# O2.net
KiCad netlist of a schematic drawn in EAGLE
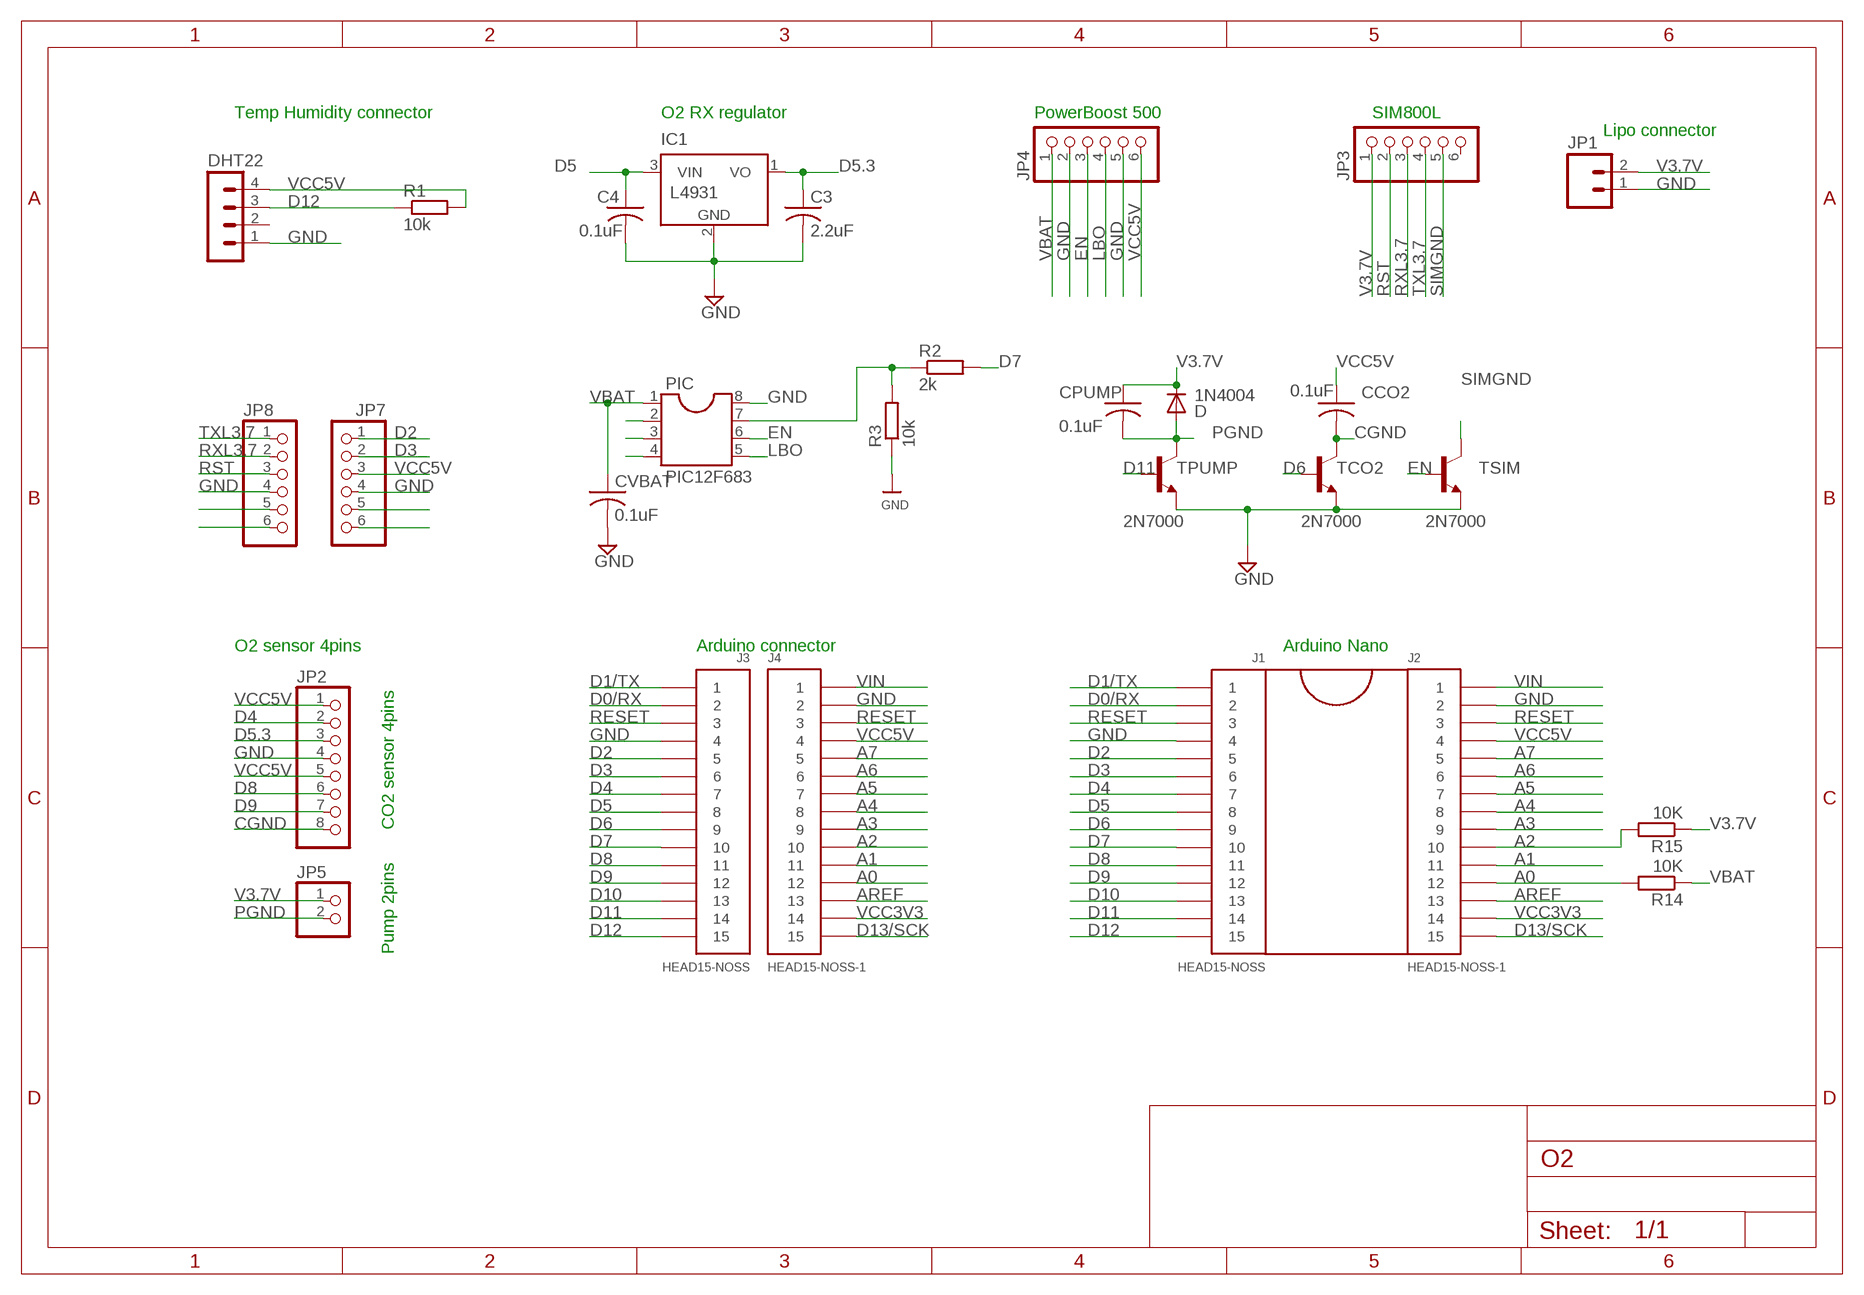
[diagram p0: schematic, sheet 1]

(export (version "E")
  (design (tool "Eeschema 10.0.6"))
  (components
    (comp (ref "C3")
      (value "2.2uF")
      (footprint "eagle-import:C025-030X050")
      (libsource (lib "eagle-import") (part "C-US025-030X050"))
    )
    (comp (ref "C4")
      (value "0.1uF")
      (footprint "eagle-import:C025-030X050")
      (libsource (lib "eagle-import") (part "C-US025-030X050"))
    )
    (comp (ref "CCO2")
      (value "0.1uF")
      (footprint "eagle-import:C025-030X050")
      (libsource (lib "eagle-import") (part "C-US025-030X050"))
    )
    (comp (ref "CPUMP")
      (value "0.1uF")
      (footprint "eagle-import:C025-030X050")
      (libsource (lib "eagle-import") (part "C-US025-030X050"))
    )
    (comp (ref "CVBAT")
      (value "0.1uF")
      (footprint "eagle-import:C025-030X050")
      (libsource (lib "eagle-import") (part "C-US025-030X050"))
    )
    (comp (ref "D")
      (value "1N4004")
      (footprint "eagle-import:DO41-10")
      (libsource (lib "eagle-import") (part "1N4004"))
    )
    (comp (ref "DHT22")
      (value "MA04-1")
      (footprint "eagle-import:MA04-1")
      (libsource (lib "eagle-import") (part "MA04-1"))
    )
    (comp (ref "IC1")
      (value "L4931")
      (footprint "eagle-import:TO92")
      (fields (field (name "MF") "NATIONAL SEMICONDUCTOR") (field (name "MPN") "LM2936Z-3.3/NOPB"))
      (libsource (lib "eagle-import") (part "LM2936?Z-3.3"))
    )
    (comp (ref "J1")
      (value "HEAD15-NOSS")
      (footprint "eagle-import:HEAD15-NOSS")
      (libsource (lib "eagle-import") (part "HEAD15-NOSS"))
    )
    (comp (ref "J2")
      (value "HEAD15-NOSS-1")
      (footprint "eagle-import:HEAD15-NOSS-1")
      (libsource (lib "eagle-import") (part "HEAD15-NOSS-1"))
    )
    (comp (ref "J3")
      (value "HEAD15-NOSS")
      (footprint "eagle-import:HEAD15-NOSS")
      (libsource (lib "eagle-import") (part "HEAD15-NOSS"))
    )
    (comp (ref "J4")
      (value "HEAD15-NOSS-1")
      (footprint "eagle-import:HEAD15-NOSS-1")
      (libsource (lib "eagle-import") (part "HEAD15-NOSS-1"))
    )
    (comp (ref "JP1")
      (value "M023.5MM")
      (footprint "eagle-import:SCREWTERMINAL-3.5MM-2")
      (libsource (lib "eagle-import") (part "M023.5MM"))
    )
    (comp (ref "JP2")
      (value "PINHD-1X8BIG")
      (footprint "eagle-import:1X08-BIG")
      (libsource (lib "eagle-import") (part "PINHD-1X8BIG"))
    )
    (comp (ref "JP3")
      (value "PINHD-1X6CB")
      (footprint "eagle-import:1X06-CLEANBIG")
      (libsource (lib "eagle-import") (part "PINHD-1X6CB"))
    )
    (comp (ref "JP4")
      (value "PINHD-1X6CB")
      (footprint "eagle-import:1X06-CLEANBIG")
      (libsource (lib "eagle-import") (part "PINHD-1X6CB"))
    )
    (comp (ref "JP5")
      (value "PINHD-1X2")
      (footprint "eagle-import:1X02")
      (libsource (lib "eagle-import") (part "PINHD-1X2"))
    )
    (comp (ref "JP7")
      (value "PINHD-1X6CB")
      (footprint "eagle-import:1X06-CLEANBIG")
      (libsource (lib "eagle-import") (part "PINHD-1X6CB"))
    )
    (comp (ref "JP8")
      (value "PINHD-1X6CB")
      (footprint "eagle-import:1X06-CLEANBIG")
      (libsource (lib "eagle-import") (part "PINHD-1X6CB"))
    )
    (comp (ref "PIC")
      (value "PIC12F683")
      (footprint "eagle-import:SOCKET-08")
      (libsource (lib "eagle-import") (part "DIL8S"))
    )
    (comp (ref "R1")
      (value "10k")
      (footprint "eagle-import:0204_5")
      (libsource (lib "eagle-import") (part "R-EU_0204/5"))
    )
    (comp (ref "R2")
      (value "2k")
      (footprint "eagle-import:0204_5")
      (libsource (lib "eagle-import") (part "R-EU_0204/5"))
    )
    (comp (ref "R3")
      (value "10k")
      (footprint "eagle-import:0204_5")
      (libsource (lib "eagle-import") (part "R-EU_0204/5"))
    )
    (comp (ref "R14")
      (value "10K")
      (footprint "eagle-import:0204_5")
      (libsource (lib "eagle-import") (part "R-EU_0204/5"))
    )
    (comp (ref "R15")
      (value "10K")
      (footprint "eagle-import:0204_5")
      (libsource (lib "eagle-import") (part "R-EU_0204/5"))
    )
    (comp (ref "TCO2")
      (value "2N7000")
      (footprint "eagle-import:TO92-EBC-OVAL")
      (libsource (lib "eagle-import") (part "2N2222"))
    )
    (comp (ref "TPUMP")
      (value "2N7000")
      (footprint "eagle-import:TO92-EBC-OVAL")
      (libsource (lib "eagle-import") (part "2N2222"))
    )
    (comp (ref "TSIM")
      (value "2N7000")
      (footprint "eagle-import:TO92-EBC-OVAL")
      (libsource (lib "eagle-import") (part "2N2222"))
    )
  )
  (nets
    (net (code "1") (name "/A0") (class "Default")
      (node (ref "J2") (pin "12") (pinfunction "12_12") (pintype "passive"))
      (node (ref "J4") (pin "12") (pinfunction "12_12") (pintype "passive"))
      (node (ref "R14") (pin "2") (pinfunction "2_2") (pintype "passive"))
    )
    (net (code "2") (name "/A1") (class "Default")
      (node (ref "J2") (pin "11") (pinfunction "11_11") (pintype "passive"))
      (node (ref "J4") (pin "11") (pinfunction "11_11") (pintype "passive"))
    )
    (net (code "3") (name "/A2") (class "Default")
      (node (ref "J2") (pin "10") (pinfunction "10_10") (pintype "passive"))
      (node (ref "J4") (pin "10") (pinfunction "10_10") (pintype "passive"))
      (node (ref "R15") (pin "2") (pinfunction "2_2") (pintype "passive"))
    )
    (net (code "4") (name "/A3") (class "Default")
      (node (ref "J2") (pin "9") (pinfunction "9_9") (pintype "passive"))
      (node (ref "J4") (pin "9") (pinfunction "9_9") (pintype "passive"))
    )
    (net (code "5") (name "/A4") (class "Default")
      (node (ref "J2") (pin "8") (pinfunction "8_8") (pintype "passive"))
      (node (ref "J4") (pin "8") (pinfunction "8_8") (pintype "passive"))
    )
    (net (code "6") (name "/A5") (class "Default")
      (node (ref "J2") (pin "7") (pinfunction "7_7") (pintype "passive"))
      (node (ref "J4") (pin "7") (pinfunction "7_7") (pintype "passive"))
    )
    (net (code "7") (name "/A6") (class "Default")
      (node (ref "J2") (pin "6") (pinfunction "6_6") (pintype "passive"))
      (node (ref "J4") (pin "6") (pinfunction "6_6") (pintype "passive"))
    )
    (net (code "8") (name "/A7") (class "Default")
      (node (ref "J2") (pin "5") (pinfunction "5_5") (pintype "passive"))
      (node (ref "J4") (pin "5") (pinfunction "5_5") (pintype "passive"))
    )
    (net (code "9") (name "/AREF") (class "Default")
      (node (ref "J2") (pin "13") (pinfunction "13_13") (pintype "passive"))
      (node (ref "J4") (pin "13") (pinfunction "13_13") (pintype "passive"))
    )
    (net (code "10") (name "/CGND") (class "Default")
      (node (ref "CCO2") (pin "2") (pinfunction "2_2") (pintype "passive"))
      (node (ref "JP2") (pin "8") (pinfunction "8_8") (pintype "passive"))
      (node (ref "TCO2") (pin "C") (pinfunction "C_C") (pintype "passive"))
    )
    (net (code "11") (name "/D0{slash}RX") (class "Default")
      (node (ref "J1") (pin "2") (pinfunction "2_2") (pintype "passive"))
      (node (ref "J3") (pin "2") (pinfunction "2_2") (pintype "passive"))
    )
    (net (code "12") (name "/D1{slash}TX") (class "Default")
      (node (ref "J1") (pin "1") (pinfunction "1_1") (pintype "passive"))
      (node (ref "J3") (pin "1") (pinfunction "1_1") (pintype "passive"))
    )
    (net (code "13") (name "/D2") (class "Default")
      (node (ref "J1") (pin "5") (pinfunction "5_5") (pintype "passive"))
      (node (ref "J3") (pin "5") (pinfunction "5_5") (pintype "passive"))
      (node (ref "JP7") (pin "1") (pinfunction "1_1") (pintype "passive"))
    )
    (net (code "14") (name "/D3") (class "Default")
      (node (ref "J1") (pin "6") (pinfunction "6_6") (pintype "passive"))
      (node (ref "J3") (pin "6") (pinfunction "6_6") (pintype "passive"))
      (node (ref "JP7") (pin "2") (pinfunction "2_2") (pintype "passive"))
    )
    (net (code "15") (name "/D4") (class "Default")
      (node (ref "J1") (pin "7") (pinfunction "7_7") (pintype "passive"))
      (node (ref "J3") (pin "7") (pinfunction "7_7") (pintype "passive"))
      (node (ref "JP2") (pin "2") (pinfunction "2_2") (pintype "passive"))
    )
    (net (code "16") (name "/D5") (class "Default")
      (node (ref "C4") (pin "1") (pinfunction "1_1") (pintype "passive"))
      (node (ref "IC1") (pin "3") (pinfunction "VIN_3") (pintype "input"))
      (node (ref "J1") (pin "8") (pinfunction "8_8") (pintype "passive"))
      (node (ref "J3") (pin "8") (pinfunction "8_8") (pintype "passive"))
    )
    (net (code "17") (name "/D5.3") (class "Default")
      (node (ref "C3") (pin "1") (pinfunction "1_1") (pintype "passive"))
      (node (ref "IC1") (pin "1") (pinfunction "VO_1") (pintype "passive"))
      (node (ref "JP2") (pin "3") (pinfunction "3_3") (pintype "passive"))
    )
    (net (code "18") (name "/D6") (class "Default")
      (node (ref "J1") (pin "9") (pinfunction "9_9") (pintype "passive"))
      (node (ref "J3") (pin "9") (pinfunction "9_9") (pintype "passive"))
      (node (ref "TCO2") (pin "B") (pinfunction "B_B") (pintype "passive"))
    )
    (net (code "19") (name "/D7") (class "Default")
      (node (ref "J1") (pin "10") (pinfunction "10_10") (pintype "passive"))
      (node (ref "J3") (pin "10") (pinfunction "10_10") (pintype "passive"))
      (node (ref "R2") (pin "2") (pinfunction "2_2") (pintype "passive"))
    )
    (net (code "20") (name "/D8") (class "Default")
      (node (ref "J1") (pin "11") (pinfunction "11_11") (pintype "passive"))
      (node (ref "J3") (pin "11") (pinfunction "11_11") (pintype "passive"))
      (node (ref "JP2") (pin "6") (pinfunction "6_6") (pintype "passive"))
    )
    (net (code "21") (name "/D9") (class "Default")
      (node (ref "J1") (pin "12") (pinfunction "12_12") (pintype "passive"))
      (node (ref "J3") (pin "12") (pinfunction "12_12") (pintype "passive"))
      (node (ref "JP2") (pin "7") (pinfunction "7_7") (pintype "passive"))
    )
    (net (code "22") (name "/D10") (class "Default")
      (node (ref "J1") (pin "13") (pinfunction "13_13") (pintype "passive"))
      (node (ref "J3") (pin "13") (pinfunction "13_13") (pintype "passive"))
    )
    (net (code "23") (name "/D11") (class "Default")
      (node (ref "J1") (pin "14") (pinfunction "14_14") (pintype "passive"))
      (node (ref "J3") (pin "14") (pinfunction "14_14") (pintype "passive"))
      (node (ref "TPUMP") (pin "B") (pinfunction "B_B") (pintype "passive"))
    )
    (net (code "24") (name "/D12") (class "Default")
      (node (ref "DHT22") (pin "3") (pinfunction "3_3") (pintype "passive"))
      (node (ref "J1") (pin "15") (pinfunction "15_15") (pintype "passive"))
      (node (ref "J3") (pin "15") (pinfunction "15_15") (pintype "passive"))
      (node (ref "R1") (pin "1") (pinfunction "1_1") (pintype "passive"))
    )
    (net (code "25") (name "/D13{slash}SCK") (class "Default")
      (node (ref "J2") (pin "15") (pinfunction "15_15") (pintype "passive"))
      (node (ref "J4") (pin "15") (pinfunction "15_15") (pintype "passive"))
    )
    (net (code "26") (name "/EN") (class "Default")
      (node (ref "JP4") (pin "3") (pinfunction "3_3") (pintype "passive"))
      (node (ref "PIC") (pin "6") (pinfunction "6_6") (pintype "passive"))
      (node (ref "TSIM") (pin "B") (pinfunction "B_B") (pintype "passive"))
    )
    (net (code "27") (name "/LBO") (class "Default")
      (node (ref "JP4") (pin "4") (pinfunction "4_4") (pintype "passive"))
      (node (ref "PIC") (pin "5") (pinfunction "5_5") (pintype "passive"))
    )
    (net (code "28") (name "/PGND") (class "Default")
      (node (ref "CPUMP") (pin "2") (pinfunction "2_2") (pintype "passive"))
      (node (ref "D") (pin "A") (pinfunction "A_A") (pintype "passive"))
      (node (ref "JP5") (pin "2") (pinfunction "2_2") (pintype "passive"))
      (node (ref "TPUMP") (pin "C") (pinfunction "C_C") (pintype "passive"))
    )
    (net (code "29") (name "/RESET") (class "Default")
      (node (ref "J1") (pin "3") (pinfunction "3_3") (pintype "passive"))
      (node (ref "J2") (pin "3") (pinfunction "3_3") (pintype "passive"))
      (node (ref "J3") (pin "3") (pinfunction "3_3") (pintype "passive"))
      (node (ref "J4") (pin "3") (pinfunction "3_3") (pintype "passive"))
    )
    (net (code "30") (name "/RST") (class "Default")
      (node (ref "JP3") (pin "2") (pinfunction "2_2") (pintype "passive"))
      (node (ref "JP8") (pin "3") (pinfunction "3_3") (pintype "passive"))
    )
    (net (code "31") (name "/RXL3.7") (class "Default")
      (node (ref "JP3") (pin "3") (pinfunction "3_3") (pintype "passive"))
      (node (ref "JP8") (pin "2") (pinfunction "2_2") (pintype "passive"))
    )
    (net (code "32") (name "/SIMGND") (class "Default")
      (node (ref "JP3") (pin "5") (pinfunction "5_5") (pintype "passive"))
      (node (ref "TSIM") (pin "C") (pinfunction "C_C") (pintype "passive"))
    )
    (net (code "33") (name "/TXL3.7") (class "Default")
      (node (ref "JP3") (pin "4") (pinfunction "4_4") (pintype "passive"))
      (node (ref "JP8") (pin "1") (pinfunction "1_1") (pintype "passive"))
    )
    (net (code "34") (name "/V3.7V") (class "Default")
      (node (ref "CPUMP") (pin "1") (pinfunction "1_1") (pintype "passive"))
      (node (ref "D") (pin "C") (pinfunction "C_C") (pintype "passive"))
      (node (ref "JP1") (pin "2") (pinfunction "2_2") (pintype "passive"))
      (node (ref "JP3") (pin "1") (pinfunction "1_1") (pintype "passive"))
      (node (ref "JP5") (pin "1") (pinfunction "1_1") (pintype "passive"))
      (node (ref "R15") (pin "1") (pinfunction "1_1") (pintype "passive"))
    )
    (net (code "35") (name "/VBAT") (class "Default")
      (node (ref "CVBAT") (pin "1") (pinfunction "1_1") (pintype "passive"))
      (node (ref "JP4") (pin "1") (pinfunction "1_1") (pintype "passive"))
      (node (ref "PIC") (pin "1") (pinfunction "1_1") (pintype "passive"))
      (node (ref "R14") (pin "1") (pinfunction "1_1") (pintype "passive"))
    )
    (net (code "36") (name "/VCC3V3") (class "Default")
      (node (ref "J2") (pin "14") (pinfunction "14_14") (pintype "passive"))
      (node (ref "J4") (pin "14") (pinfunction "14_14") (pintype "passive"))
    )
    (net (code "37") (name "/VCC5V") (class "Default")
      (node (ref "CCO2") (pin "1") (pinfunction "1_1") (pintype "passive"))
      (node (ref "DHT22") (pin "4") (pinfunction "4_4") (pintype "passive"))
      (node (ref "J2") (pin "4") (pinfunction "4_4") (pintype "passive"))
      (node (ref "J4") (pin "4") (pinfunction "4_4") (pintype "passive"))
      (node (ref "JP2") (pin "1") (pinfunction "1_1") (pintype "passive"))
      (node (ref "JP2") (pin "5") (pinfunction "5_5") (pintype "passive"))
      (node (ref "JP4") (pin "6") (pinfunction "6_6") (pintype "passive"))
      (node (ref "JP7") (pin "3") (pinfunction "3_3") (pintype "passive"))
      (node (ref "R1") (pin "2") (pinfunction "2_2") (pintype "passive"))
    )
    (net (code "38") (name "/VIN") (class "Default")
      (node (ref "J2") (pin "1") (pinfunction "1_1") (pintype "passive"))
      (node (ref "J4") (pin "1") (pinfunction "1_1") (pintype "passive"))
    )
    (net (code "39") (name "GND") (class "Default")
      (node (ref "C3") (pin "2") (pinfunction "2_2") (pintype "passive"))
      (node (ref "C4") (pin "2") (pinfunction "2_2") (pintype "passive"))
      (node (ref "CVBAT") (pin "2") (pinfunction "2_2") (pintype "passive"))
      (node (ref "DHT22") (pin "1") (pinfunction "1_1") (pintype "passive"))
      (node (ref "IC1") (pin "2") (pinfunction "GND_2") (pintype "passive"))
      (node (ref "J1") (pin "4") (pinfunction "4_4") (pintype "passive"))
      (node (ref "J2") (pin "2") (pinfunction "2_2") (pintype "passive"))
      (node (ref "J3") (pin "4") (pinfunction "4_4") (pintype "passive"))
      (node (ref "J4") (pin "2") (pinfunction "2_2") (pintype "passive"))
      (node (ref "JP1") (pin "1") (pinfunction "1_1") (pintype "passive"))
      (node (ref "JP2") (pin "4") (pinfunction "4_4") (pintype "passive"))
      (node (ref "JP4") (pin "2") (pinfunction "2_2") (pintype "passive"))
      (node (ref "JP4") (pin "5") (pinfunction "5_5") (pintype "passive"))
      (node (ref "JP7") (pin "4") (pinfunction "4_4") (pintype "passive"))
      (node (ref "JP8") (pin "4") (pinfunction "4_4") (pintype "passive"))
      (node (ref "PIC") (pin "8") (pinfunction "8_8") (pintype "passive"))
      (node (ref "R3") (pin "1") (pinfunction "1_1") (pintype "passive"))
      (node (ref "TCO2") (pin "E") (pinfunction "E_E") (pintype "passive"))
      (node (ref "TPUMP") (pin "E") (pinfunction "E_E") (pintype "passive"))
      (node (ref "TSIM") (pin "E") (pinfunction "E_E") (pintype "passive"))
    )
    (net (code "40") (name "Net-(PIC-Pad7)") (class "Default")
      (node (ref "PIC") (pin "7") (pinfunction "7_7") (pintype "passive"))
      (node (ref "R2") (pin "1") (pinfunction "1_1") (pintype "passive"))
      (node (ref "R3") (pin "2") (pinfunction "2_2") (pintype "passive"))
    )
    (net (code "41") (name "unconnected-(DHT22-Pad2)") (class "Default")
      (node (ref "DHT22") (pin "2") (pinfunction "2_2") (pintype "passive"))
    )
    (net (code "42") (name "unconnected-(JP3-Pad6)") (class "Default")
      (node (ref "JP3") (pin "6") (pinfunction "6_6") (pintype "passive"))
    )
    (net (code "43") (name "unconnected-(JP7-Pad5)") (class "Default")
      (node (ref "JP7") (pin "5") (pinfunction "5_5") (pintype "passive"))
    )
    (net (code "44") (name "unconnected-(JP7-Pad6)") (class "Default")
      (node (ref "JP7") (pin "6") (pinfunction "6_6") (pintype "passive"))
    )
    (net (code "45") (name "unconnected-(JP8-Pad5)") (class "Default")
      (node (ref "JP8") (pin "5") (pinfunction "5_5") (pintype "passive"))
    )
    (net (code "46") (name "unconnected-(JP8-Pad6)") (class "Default")
      (node (ref "JP8") (pin "6") (pinfunction "6_6") (pintype "passive"))
    )
    (net (code "47") (name "unconnected-(PIC-Pad2)") (class "Default")
      (node (ref "PIC") (pin "2") (pinfunction "2_2") (pintype "passive"))
    )
    (net (code "48") (name "unconnected-(PIC-Pad3)") (class "Default")
      (node (ref "PIC") (pin "3") (pinfunction "3_3") (pintype "passive"))
    )
    (net (code "49") (name "unconnected-(PIC-Pad4)") (class "Default")
      (node (ref "PIC") (pin "4") (pinfunction "4_4") (pintype "passive"))
    )
  )
)
